# CTRL_LOGIC.net
KiCad netlist of a schematic drawn in Altium Designer
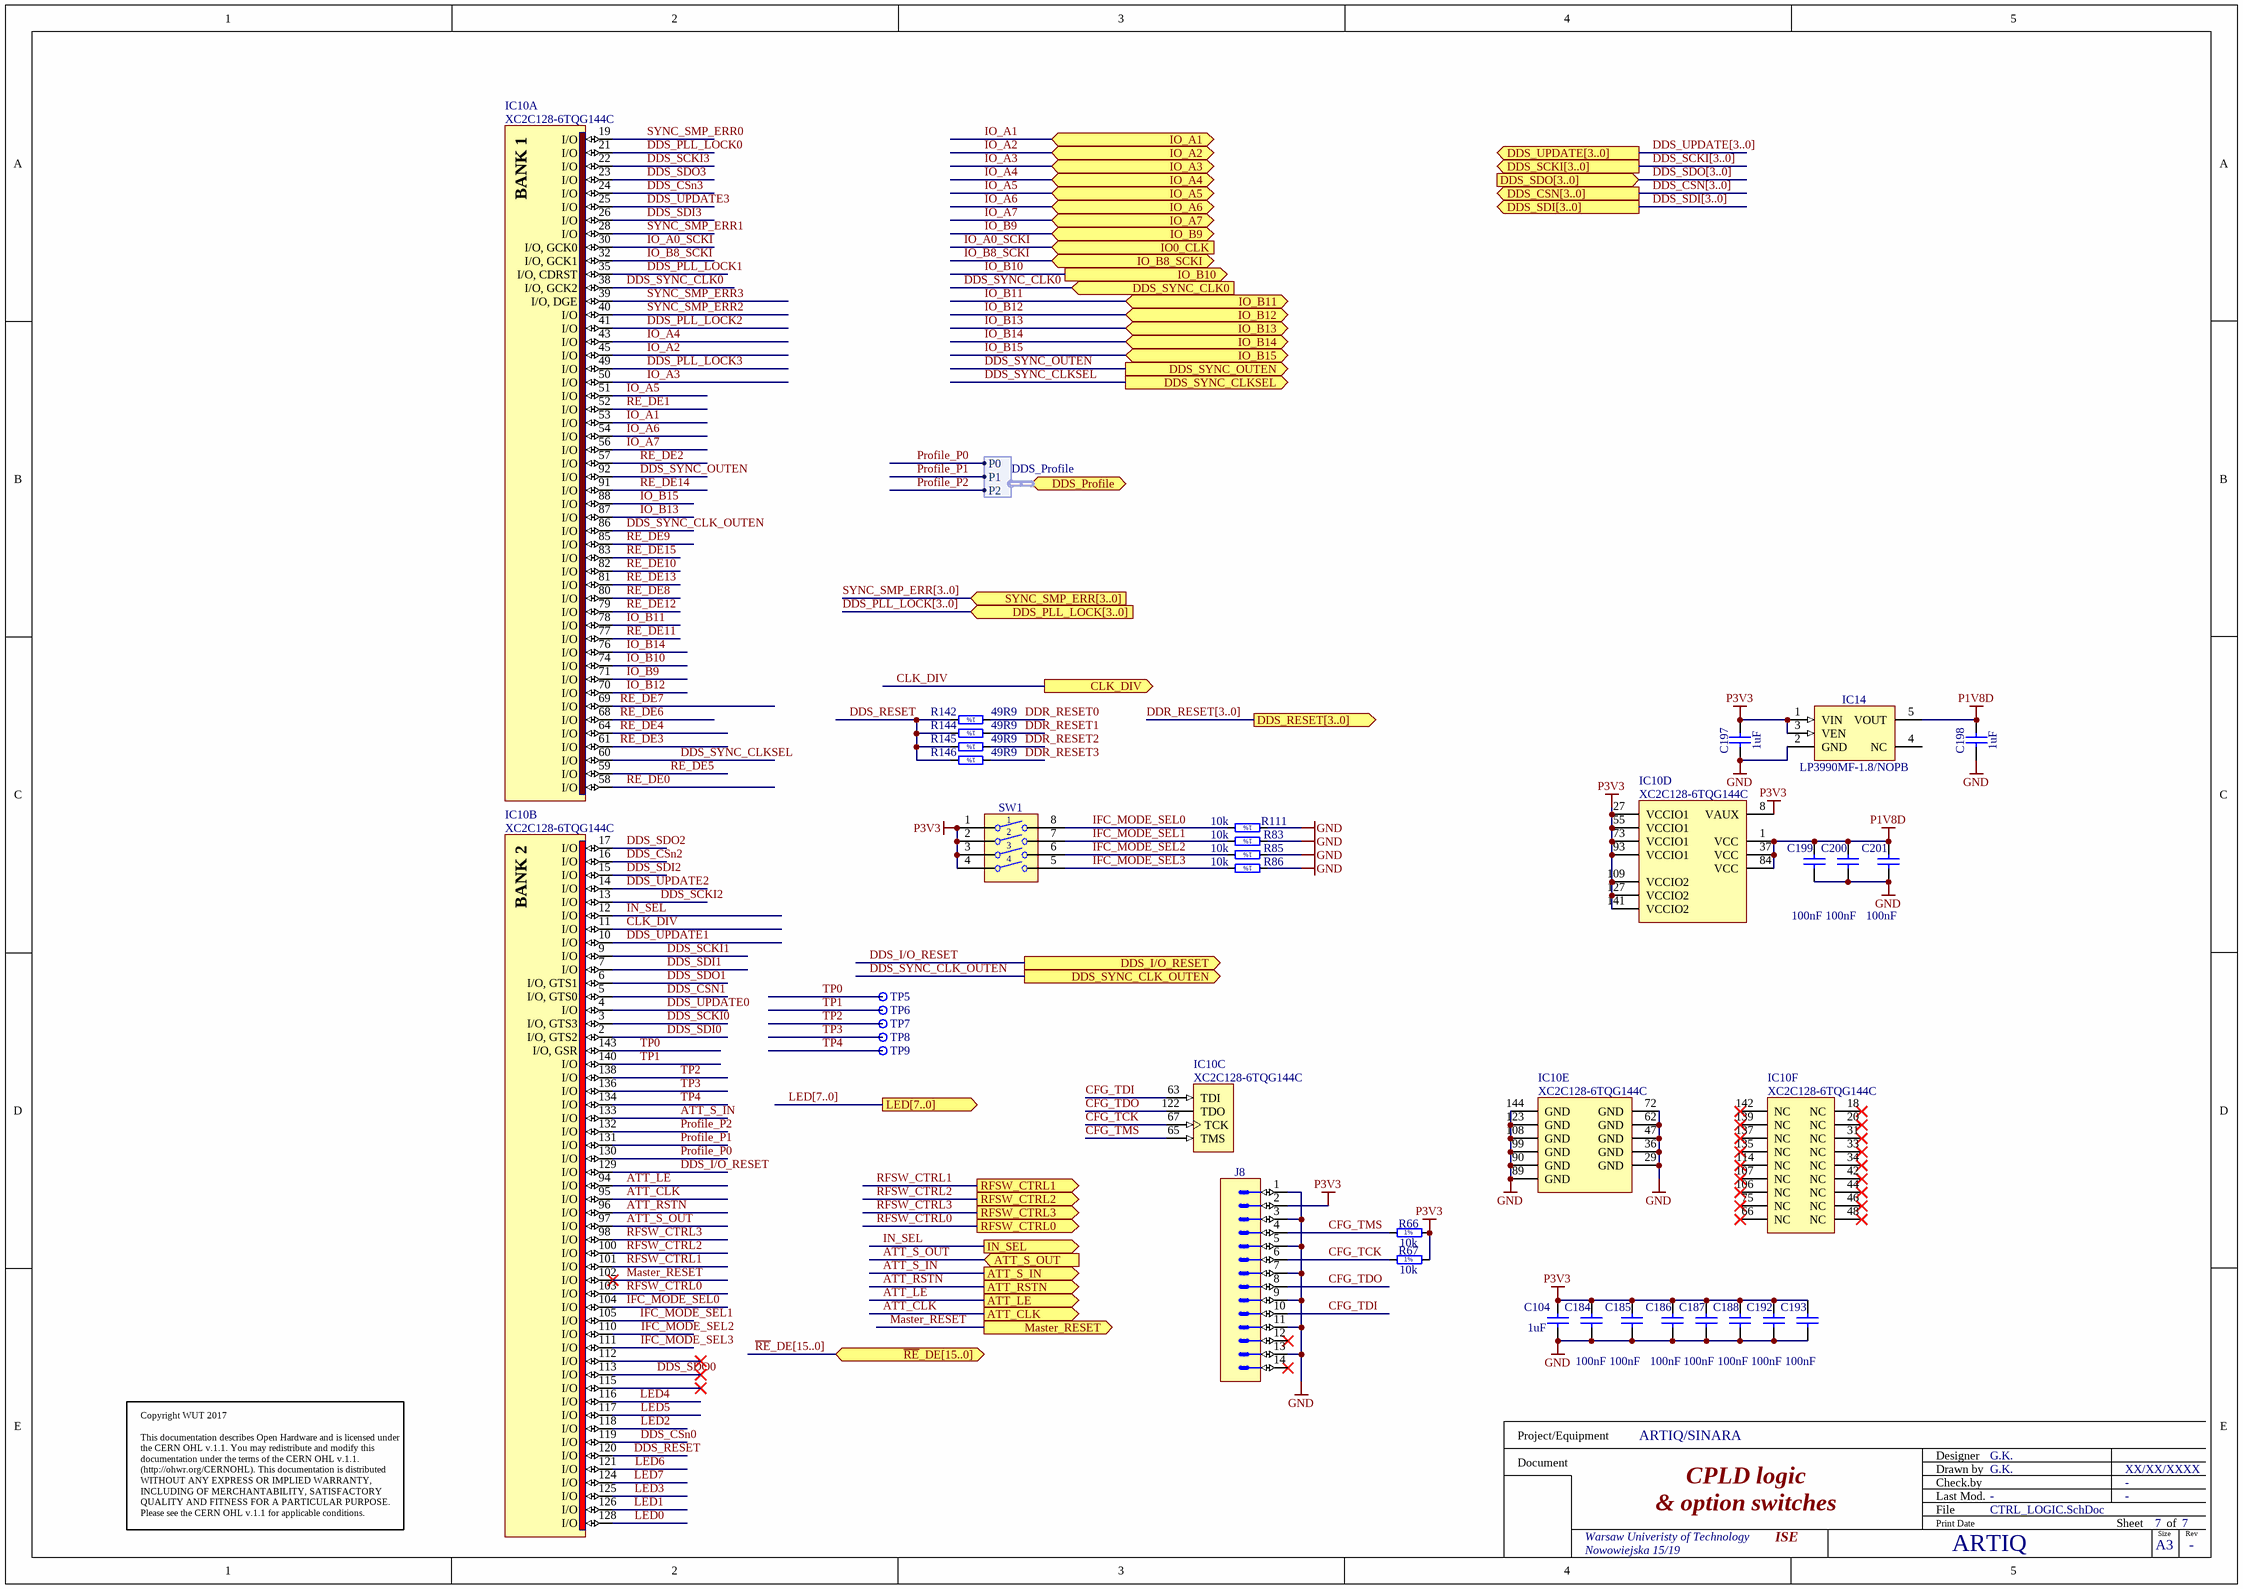
[diagram p0: CTRL_LOGIC.SchDoc]

(export (version "E")
  (design (tool "Eeschema 10.0.6"))
  (components
    (comp (ref "C104")
      (value "1uF")
      (footprint "CAPC1005X55N")
      (description "Non-polarised capacitor")
      (fields
        (field (name "PART NUMBER") "CC0402_1UF_16V_10%_X5R")
        (field (name "VOLTAGE") "16V")
        (field (name "AUTHOR") "CERN DEM JLC")
      )
      (libsource (lib "Capacitors") (part "Capacitor - non polarized"))
    )
    (comp (ref "C184")
      (value "100nF")
      (footprint "CAPC1005X55N")
      (description "Non-polarised capacitor")
      (fields
        (field (name "PART NUMBER") "CC0402_100NF_16V_10%_X5R")
        (field (name "VOLTAGE") "16V")
        (field (name "AUTHOR") "CERN DEM JLC")
      )
      (libsource (lib "Capacitors") (part "Capacitor - non polarized"))
    )
    (comp (ref "C185")
      (value "100nF")
      (footprint "CAPC1005X55N")
      (description "Non-polarised capacitor")
      (fields
        (field (name "PART NUMBER") "CC0402_100NF_16V_10%_X5R")
        (field (name "VOLTAGE") "16V")
        (field (name "AUTHOR") "CERN DEM JLC")
      )
      (libsource (lib "Capacitors") (part "Capacitor - non polarized"))
    )
    (comp (ref "C186")
      (value "100nF")
      (footprint "CAPC1005X55N")
      (description "Non-polarised capacitor")
      (fields
        (field (name "PART NUMBER") "CC0402_100NF_16V_10%_X5R")
        (field (name "VOLTAGE") "16V")
        (field (name "AUTHOR") "CERN DEM JLC")
      )
      (libsource (lib "Capacitors") (part "Capacitor - non polarized"))
    )
    (comp (ref "C187")
      (value "100nF")
      (footprint "CAPC1005X55N")
      (description "Non-polarised capacitor")
      (fields
        (field (name "PART NUMBER") "CC0402_100NF_16V_10%_X5R")
        (field (name "VOLTAGE") "16V")
        (field (name "AUTHOR") "CERN DEM JLC")
      )
      (libsource (lib "Capacitors") (part "Capacitor - non polarized"))
    )
    (comp (ref "C188")
      (value "100nF")
      (footprint "CAPC1005X55N")
      (description "Non-polarised capacitor")
      (fields
        (field (name "PART NUMBER") "CC0402_100NF_16V_10%_X5R")
        (field (name "VOLTAGE") "16V")
        (field (name "AUTHOR") "CERN DEM JLC")
      )
      (libsource (lib "Capacitors") (part "Capacitor - non polarized"))
    )
    (comp (ref "C192")
      (value "100nF")
      (footprint "CAPC1005X55N")
      (description "Non-polarised capacitor")
      (fields
        (field (name "PART NUMBER") "CC0402_100NF_16V_10%_X5R")
        (field (name "VOLTAGE") "16V")
        (field (name "AUTHOR") "CERN DEM JLC")
      )
      (libsource (lib "Capacitors") (part "Capacitor - non polarized"))
    )
    (comp (ref "C193")
      (value "100nF")
      (footprint "CAPC1005X55N")
      (description "Non-polarised capacitor")
      (fields
        (field (name "PART NUMBER") "CC0402_100NF_16V_10%_X5R")
        (field (name "VOLTAGE") "16V")
        (field (name "AUTHOR") "CERN DEM JLC")
      )
      (libsource (lib "Capacitors") (part "Capacitor - non polarized"))
    )
    (comp (ref "C197")
      (value "1uF")
      (footprint "CAPC1005X55N")
      (description "Non-polarised capacitor")
      (fields
        (field (name "PART NUMBER") "CC0402_1UF_16V_10%_X5R")
        (field (name "VOLTAGE") "16V")
        (field (name "AUTHOR") "CERN DEM JLC")
      )
      (libsource (lib "Capacitors") (part "Capacitor - non polarized"))
    )
    (comp (ref "C198")
      (value "1uF")
      (footprint "CAPC1005X55N")
      (description "Non-polarised capacitor")
      (fields
        (field (name "PART NUMBER") "CC0402_1UF_16V_10%_X5R")
        (field (name "VOLTAGE") "16V")
        (field (name "AUTHOR") "CERN DEM JLC")
      )
      (libsource (lib "Capacitors") (part "Capacitor - non polarized"))
    )
    (comp (ref "C199")
      (value "100nF")
      (footprint "CAPC1005X55N")
      (description "Non-polarised capacitor")
      (fields
        (field (name "PART NUMBER") "CC0402_100NF_16V_10%_X5R")
        (field (name "VOLTAGE") "16V")
        (field (name "AUTHOR") "CERN DEM JLC")
      )
      (libsource (lib "Capacitors") (part "Capacitor - non polarized"))
    )
    (comp (ref "C200")
      (value "100nF")
      (footprint "CAPC1005X55N")
      (description "Non-polarised capacitor")
      (fields
        (field (name "PART NUMBER") "CC0402_100NF_16V_10%_X5R")
        (field (name "VOLTAGE") "16V")
        (field (name "AUTHOR") "CERN DEM JLC")
      )
      (libsource (lib "Capacitors") (part "Capacitor - non polarized"))
    )
    (comp (ref "C201")
      (value "100nF")
      (footprint "CAPC1005X55N")
      (description "Non-polarised capacitor")
      (fields
        (field (name "PART NUMBER") "CC0402_100NF_16V_10%_X5R")
        (field (name "VOLTAGE") "16V")
        (field (name "AUTHOR") "CERN DEM JLC")
      )
      (libsource (lib "Capacitors") (part "Capacitor - non polarized"))
    )
    (comp (ref "IC10")
      (value "XC2C128-6TQG144C")
      (footprint "QFP50P2200X2200X160-144N")
      (description "CoolRunner-II 1.8V, 128 Macrocell CPLD, 100 User I/Os, 144-Pin TQFP, Commercial Grade, Pb-Free")
      (fields (field (name "MANUFACTURER") "XILINX") (field (name "AUTHOR") "CERN DEM JLC"))
      (libsource (lib "ICs And Semiconductors") (part "XC2C128-6TQG144C"))
    )
    (comp (ref "IC14")
      (value "LP3990MF-1.8/NOPB")
      (footprint "SOT95P284X122-5N")
      (description "1.8V, 150mA Linear Voltage Regulator For Digital Applications")
      (fields (field (name "MANUFACTURER") "TEXAS INSTRUMENTS") (field (name "AUTHOR") "CERN DEM JLC"))
      (libsource (lib "ICs And Semiconductors") (part "LP3990MF"))
    )
    (comp (ref "J8")
      (value "Milli-Grid™")
      (footprint "MOLEX_87832-1420")
      (description "Connector 14 Male")
      (fields
        (field (name "PART NUMBER") "MOLEX_87832-1420")
        (field (name "MANUFACTURER") "MOLEX")
        (field (name "AUTHOR") "CERN DEM JLC")
      )
      (libsource (lib "Connectors") (part "Connector 14 Male"))
    )
    (comp (ref "R66")
      (value "10k")
      (footprint "RESC1005X40N")
      (description "Resistor - 1%")
      (fields
        (field (name "PART NUMBER") "R0402_10K_1%_0.0625W_100PPM")
        (field (name "POWER") "0.0625W")
        (field (name "AUTHOR") "CERN DEM JLC")
      )
      (libsource (lib "Resistors") (part "Resistor - 1%"))
    )
    (comp (ref "R67")
      (value "10k")
      (footprint "RESC1005X40N")
      (description "Resistor - 1%")
      (fields
        (field (name "PART NUMBER") "R0402_10K_1%_0.0625W_100PPM")
        (field (name "POWER") "0.0625W")
        (field (name "AUTHOR") "CERN DEM JLC")
      )
      (libsource (lib "Resistors") (part "Resistor - 1%"))
    )
    (comp (ref "R83")
      (value "10k")
      (footprint "RESC1005X40N")
      (description "Resistor - 1%")
      (fields
        (field (name "PART NUMBER") "R0402_10K_1%_0.0625W_100PPM")
        (field (name "POWER") "0.0625W")
        (field (name "AUTHOR") "CERN DEM JLC")
      )
      (libsource (lib "Resistors") (part "Resistor - 1%"))
    )
    (comp (ref "R85")
      (value "10k")
      (footprint "RESC1005X40N")
      (description "Resistor - 1%")
      (fields
        (field (name "PART NUMBER") "R0402_10K_1%_0.0625W_100PPM")
        (field (name "POWER") "0.0625W")
        (field (name "AUTHOR") "CERN DEM JLC")
      )
      (libsource (lib "Resistors") (part "Resistor - 1%"))
    )
    (comp (ref "R86")
      (value "10k")
      (footprint "RESC1005X40N")
      (description "Resistor - 1%")
      (fields
        (field (name "PART NUMBER") "R0402_10K_1%_0.0625W_100PPM")
        (field (name "POWER") "0.0625W")
        (field (name "AUTHOR") "CERN DEM JLC")
      )
      (libsource (lib "Resistors") (part "Resistor - 1%"))
    )
    (comp (ref "R111")
      (value "10k")
      (footprint "RESC1005X40N")
      (description "Resistor - 1%")
      (fields
        (field (name "PART NUMBER") "R0402_10K_1%_0.0625W_100PPM")
        (field (name "POWER") "0.0625W")
        (field (name "AUTHOR") "CERN DEM JLC")
      )
      (libsource (lib "Resistors") (part "Resistor - 1%"))
    )
    (comp (ref "R142")
      (value "49R9")
      (footprint "RESC1005X40N")
      (description "Resistor - 1%")
      (fields
        (field (name "PART NUMBER") "R0402_49R9_1%_0.0625W_100PPM")
        (field (name "POWER") "0.0625W")
        (field (name "AUTHOR") "CERN DEM JLC")
      )
      (libsource (lib "Resistors") (part "Resistor - 1%"))
    )
    (comp (ref "R144")
      (value "49R9")
      (footprint "RESC1005X40N")
      (description "Resistor - 1%")
      (fields
        (field (name "PART NUMBER") "R0402_49R9_1%_0.0625W_100PPM")
        (field (name "POWER") "0.0625W")
        (field (name "AUTHOR") "CERN DEM JLC")
      )
      (libsource (lib "Resistors") (part "Resistor - 1%"))
    )
    (comp (ref "R145")
      (value "49R9")
      (footprint "RESC1005X40N")
      (description "Resistor - 1%")
      (fields
        (field (name "PART NUMBER") "R0402_49R9_1%_0.0625W_100PPM")
        (field (name "POWER") "0.0625W")
        (field (name "AUTHOR") "CERN DEM JLC")
      )
      (libsource (lib "Resistors") (part "Resistor - 1%"))
    )
    (comp (ref "R146")
      (value "49R9")
      (footprint "RESC1005X40N")
      (description "Resistor - 1%")
      (fields
        (field (name "PART NUMBER") "R0402_49R9_1%_0.0625W_100PPM")
        (field (name "POWER") "0.0625W")
        (field (name "AUTHOR") "CERN DEM JLC")
      )
      (libsource (lib "Resistors") (part "Resistor - 1%"))
    )
    (comp (ref "SW1")
      (value "Switch")
      (footprint "SW_OMRON_A6S-4102-H")
      (description "4 Ways SPST DIP Switch")
      (fields
        (field (name "PART NUMBER") "SW_OMRON_A6S-4102-H")
        (field (name "MANUFACTURER") "OMRON")
        (field (name "AUTHOR") "CERN DEM JMW")
      )
      (libsource (lib "Eletro-mechanical") (part "SW 4x SPST DIP Switch"))
    )
    (comp (ref "TP5")
      (value "Test Point")
      (footprint "TPS127")
      (fields (field (name "PART NUMBER") "SMD_PAD_1.27X1.27MM") (field (name "AUTHOR") "CERN DEM JLC"))
      (libsource (lib "Eletro-mechanical") (part "Test Point"))
    )
    (comp (ref "TP6")
      (value "Test Point")
      (footprint "TPS127")
      (fields (field (name "PART NUMBER") "SMD_PAD_1.27X1.27MM") (field (name "AUTHOR") "CERN DEM JLC"))
      (libsource (lib "Eletro-mechanical") (part "Test Point"))
    )
    (comp (ref "TP7")
      (value "Test Point")
      (footprint "TPS127")
      (fields (field (name "PART NUMBER") "SMD_PAD_1.27X1.27MM") (field (name "AUTHOR") "CERN DEM JLC"))
      (libsource (lib "Eletro-mechanical") (part "Test Point"))
    )
    (comp (ref "TP8")
      (value "Test Point")
      (footprint "TPS127")
      (fields (field (name "PART NUMBER") "SMD_PAD_1.27X1.27MM") (field (name "AUTHOR") "CERN DEM JLC"))
      (libsource (lib "Eletro-mechanical") (part "Test Point"))
    )
    (comp (ref "TP9")
      (value "Test Point")
      (footprint "TPS127")
      (fields (field (name "PART NUMBER") "SMD_PAD_1.27X1.27MM") (field (name "AUTHOR") "CERN DEM JLC"))
      (libsource (lib "Eletro-mechanical") (part "Test Point"))
    )
  )
  (nets
    (net (code "5") (name "/ATT_CLK") (class "Default")
      (node (ref "IC10") (pin "95") (pinfunction "I/O_95") (pintype "bidirectional"))
    )
    (net (code "6") (name "/ATT_LE") (class "Default")
      (node (ref "IC10") (pin "94") (pinfunction "I/O_94") (pintype "bidirectional"))
    )
    (net (code "7") (name "/ATT_RSTN") (class "Default")
      (node (ref "IC10") (pin "96") (pinfunction "I/O_96") (pintype "bidirectional"))
    )
    (net (code "8") (name "/ATT_S_IN") (class "Default")
      (node (ref "IC10") (pin "133") (pinfunction "I/O_133") (pintype "bidirectional"))
    )
    (net (code "9") (name "/ATT_S_OUT") (class "Default")
      (node (ref "IC10") (pin "97") (pinfunction "I/O_97") (pintype "bidirectional"))
    )
    (net (code "10") (name "/CFG_TCK") (class "Default")
      (node (ref "IC10") (pin "67") (pinfunction "TCK_67") (pintype "input"))
      (node (ref "J8") (pin "6") (pinfunction "6_6") (pintype "bidirectional"))
      (node (ref "R67") (pin "1") (pinfunction "1_1") (pintype "passive"))
    )
    (net (code "11") (name "/CFG_TDI") (class "Default")
      (node (ref "IC10") (pin "63") (pinfunction "TDI_63") (pintype "input"))
      (node (ref "J8") (pin "10") (pinfunction "10_10") (pintype "bidirectional"))
    )
    (net (code "12") (name "/CFG_TDO") (class "Default")
      (node (ref "IC10") (pin "122") (pinfunction "TDO_122") (pintype "passive"))
      (node (ref "J8") (pin "8") (pinfunction "8_8") (pintype "bidirectional"))
    )
    (net (code "13") (name "/CFG_TMS") (class "Default")
      (node (ref "IC10") (pin "65") (pinfunction "TMS_65") (pintype "input"))
      (node (ref "J8") (pin "4") (pinfunction "4_4") (pintype "bidirectional"))
      (node (ref "R66") (pin "1") (pinfunction "1_1") (pintype "passive"))
    )
    (net (code "14") (name "/CLK_DIV") (class "Default")
      (node (ref "IC10") (pin "11") (pinfunction "I/O_11") (pintype "bidirectional"))
    )
    (net (code "15") (name "/DDR_RESET0") (class "Default")
      (node (ref "R142") (pin "1") (pinfunction "1_1") (pintype "passive"))
    )
    (net (code "16") (name "/DDR_RESET1") (class "Default")
      (node (ref "R144") (pin "1") (pinfunction "1_1") (pintype "passive"))
    )
    (net (code "17") (name "/DDR_RESET2") (class "Default")
      (node (ref "R145") (pin "1") (pinfunction "1_1") (pintype "passive"))
    )
    (net (code "18") (name "/DDR_RESET3") (class "Default")
      (node (ref "R146") (pin "1") (pinfunction "1_1") (pintype "passive"))
    )
    (net (code "20") (name "/DDS_CSN1") (class "Default")
      (node (ref "IC10") (pin "5") (pinfunction "I/O,_GTS0_5") (pintype "bidirectional"))
    )
    (net (code "22") (name "/DDS_CSn0") (class "Default")
      (node (ref "IC10") (pin "119") (pinfunction "I/O_119") (pintype "bidirectional"))
    )
    (net (code "23") (name "/DDS_CSn2") (class "Default")
      (node (ref "IC10") (pin "16") (pinfunction "I/O_16") (pintype "bidirectional"))
    )
    (net (code "24") (name "/DDS_CSn3") (class "Default")
      (node (ref "IC10") (pin "24") (pinfunction "I/O_24") (pintype "bidirectional"))
    )
    (net (code "25") (name "/DDS_I{slash}O_RESET") (class "Default")
      (node (ref "IC10") (pin "129") (pinfunction "I/O_129") (pintype "bidirectional"))
    )
    (net (code "26") (name "/DDS_PLL_LOCK0") (class "Default")
      (node (ref "IC10") (pin "21") (pinfunction "I/O_21") (pintype "bidirectional"))
    )
    (net (code "27") (name "/DDS_PLL_LOCK1") (class "Default")
      (node (ref "IC10") (pin "35") (pinfunction "I/O,_CDRST_35") (pintype "bidirectional"))
    )
    (net (code "28") (name "/DDS_PLL_LOCK2") (class "Default")
      (node (ref "IC10") (pin "41") (pinfunction "I/O_41") (pintype "bidirectional"))
    )
    (net (code "29") (name "/DDS_PLL_LOCK3") (class "Default")
      (node (ref "IC10") (pin "49") (pinfunction "I/O_49") (pintype "bidirectional"))
    )
    (net (code "31") (name "/DDS_RESET") (class "Default")
      (node (ref "IC10") (pin "120") (pinfunction "I/O_120") (pintype "bidirectional"))
      (node (ref "R142") (pin "2") (pinfunction "2_2") (pintype "passive"))
      (node (ref "R144") (pin "2") (pinfunction "2_2") (pintype "passive"))
      (node (ref "R145") (pin "2") (pinfunction "2_2") (pintype "passive"))
      (node (ref "R146") (pin "2") (pinfunction "2_2") (pintype "passive"))
    )
    (net (code "32") (name "/DDS_SCKI0") (class "Default")
      (node (ref "IC10") (pin "3") (pinfunction "I/O,_GTS3_3") (pintype "bidirectional"))
    )
    (net (code "33") (name "/DDS_SCKI1") (class "Default")
      (node (ref "IC10") (pin "9") (pinfunction "I/O_9") (pintype "bidirectional"))
    )
    (net (code "34") (name "/DDS_SCKI2") (class "Default")
      (node (ref "IC10") (pin "13") (pinfunction "I/O_13") (pintype "bidirectional"))
    )
    (net (code "35") (name "/DDS_SCKI3") (class "Default")
      (node (ref "IC10") (pin "22") (pinfunction "I/O_22") (pintype "bidirectional"))
    )
    (net (code "37") (name "/DDS_SDI0") (class "Default")
      (node (ref "IC10") (pin "2") (pinfunction "I/O,_GTS2_2") (pintype "bidirectional"))
    )
    (net (code "38") (name "/DDS_SDI1") (class "Default")
      (node (ref "IC10") (pin "7") (pinfunction "I/O_7") (pintype "bidirectional"))
    )
    (net (code "39") (name "/DDS_SDI2") (class "Default")
      (node (ref "IC10") (pin "15") (pinfunction "I/O_15") (pintype "bidirectional"))
    )
    (net (code "40") (name "/DDS_SDI3") (class "Default")
      (node (ref "IC10") (pin "26") (pinfunction "I/O_26") (pintype "bidirectional"))
    )
    (net (code "42") (name "/DDS_SDO0") (class "Default")
      (node (ref "IC10") (pin "113") (pinfunction "I/O_113") (pintype "bidirectional+no_connect"))
    )
    (net (code "43") (name "/DDS_SDO1") (class "Default")
      (node (ref "IC10") (pin "6") (pinfunction "I/O,_GTS1_6") (pintype "bidirectional"))
    )
    (net (code "44") (name "/DDS_SDO2") (class "Default")
      (node (ref "IC10") (pin "17") (pinfunction "I/O_17") (pintype "bidirectional"))
    )
    (net (code "45") (name "/DDS_SDO3") (class "Default")
      (node (ref "IC10") (pin "23") (pinfunction "I/O_23") (pintype "bidirectional"))
    )
    (net (code "47") (name "/DDS_SYNC_CLK0") (class "Default")
      (node (ref "IC10") (pin "38") (pinfunction "I/O,_GCK2_38") (pintype "bidirectional"))
    )
    (net (code "48") (name "/DDS_SYNC_CLKSEL") (class "Default")
      (node (ref "IC10") (pin "60") (pinfunction "I/O_60") (pintype "bidirectional"))
    )
    (net (code "49") (name "/DDS_SYNC_CLK_OUTEN") (class "Default")
      (node (ref "IC10") (pin "86") (pinfunction "I/O_86") (pintype "bidirectional"))
    )
    (net (code "50") (name "/DDS_SYNC_OUTEN") (class "Default")
      (node (ref "IC10") (pin "92") (pinfunction "I/O_92") (pintype "bidirectional"))
    )
    (net (code "51") (name "/DDS_UPDATE0") (class "Default")
      (node (ref "IC10") (pin "4") (pinfunction "I/O_4") (pintype "bidirectional"))
    )
    (net (code "52") (name "/DDS_UPDATE1") (class "Default")
      (node (ref "IC10") (pin "10") (pinfunction "I/O_10") (pintype "bidirectional"))
    )
    (net (code "53") (name "/DDS_UPDATE2") (class "Default")
      (node (ref "IC10") (pin "14") (pinfunction "I/O_14") (pintype "bidirectional"))
    )
    (net (code "54") (name "/DDS_UPDATE3") (class "Default")
      (node (ref "IC10") (pin "25") (pinfunction "I/O_25") (pintype "bidirectional"))
    )
    (net (code "56") (name "/IFC_MODE_SEL0") (class "Default")
      (node (ref "IC10") (pin "104") (pinfunction "I/O_104") (pintype "bidirectional"))
      (node (ref "R111") (pin "2") (pinfunction "2_2") (pintype "passive"))
      (node (ref "SW1") (pin "8") (pinfunction "8_8") (pintype "passive"))
    )
    (net (code "57") (name "/IFC_MODE_SEL1") (class "Default")
      (node (ref "IC10") (pin "105") (pinfunction "I/O_105") (pintype "bidirectional"))
      (node (ref "R83") (pin "2") (pinfunction "2_2") (pintype "passive"))
      (node (ref "SW1") (pin "7") (pinfunction "7_7") (pintype "passive"))
    )
    (net (code "58") (name "/IFC_MODE_SEL2") (class "Default")
      (node (ref "IC10") (pin "110") (pinfunction "I/O_110") (pintype "bidirectional"))
      (node (ref "R85") (pin "2") (pinfunction "2_2") (pintype "passive"))
      (node (ref "SW1") (pin "6") (pinfunction "6_6") (pintype "passive"))
    )
    (net (code "59") (name "/IFC_MODE_SEL3") (class "Default")
      (node (ref "IC10") (pin "111") (pinfunction "I/O_111") (pintype "bidirectional"))
      (node (ref "R86") (pin "2") (pinfunction "2_2") (pintype "passive"))
      (node (ref "SW1") (pin "5") (pinfunction "5_5") (pintype "passive"))
    )
    (net (code "60") (name "/IN_SEL") (class "Default")
      (node (ref "IC10") (pin "12") (pinfunction "I/O_12") (pintype "bidirectional"))
    )
    (net (code "61") (name "/IO_A0_SCKI") (class "Default")
      (node (ref "IC10") (pin "30") (pinfunction "I/O,_GCK0_30") (pintype "bidirectional"))
    )
    (net (code "62") (name "/IO_A1") (class "Default")
      (node (ref "IC10") (pin "53") (pinfunction "I/O_53") (pintype "bidirectional"))
    )
    (net (code "63") (name "/IO_A2") (class "Default")
      (node (ref "IC10") (pin "45") (pinfunction "I/O_45") (pintype "bidirectional"))
    )
    (net (code "64") (name "/IO_A3") (class "Default")
      (node (ref "IC10") (pin "50") (pinfunction "I/O_50") (pintype "bidirectional"))
    )
    (net (code "65") (name "/IO_A4") (class "Default")
      (node (ref "IC10") (pin "43") (pinfunction "I/O_43") (pintype "bidirectional"))
    )
    (net (code "66") (name "/IO_A5") (class "Default")
      (node (ref "IC10") (pin "51") (pinfunction "I/O_51") (pintype "bidirectional"))
    )
    (net (code "67") (name "/IO_A6") (class "Default")
      (node (ref "IC10") (pin "54") (pinfunction "I/O_54") (pintype "bidirectional"))
    )
    (net (code "68") (name "/IO_A7") (class "Default")
      (node (ref "IC10") (pin "56") (pinfunction "I/O_56") (pintype "bidirectional"))
    )
    (net (code "69") (name "/IO_B8_SCKI") (class "Default")
      (node (ref "IC10") (pin "32") (pinfunction "I/O,_GCK1_32") (pintype "bidirectional"))
    )
    (net (code "70") (name "/IO_B9") (class "Default")
      (node (ref "IC10") (pin "71") (pinfunction "I/O_71") (pintype "bidirectional"))
    )
    (net (code "71") (name "/IO_B10") (class "Default")
      (node (ref "IC10") (pin "74") (pinfunction "I/O_74") (pintype "bidirectional"))
    )
    (net (code "72") (name "/IO_B11") (class "Default")
      (node (ref "IC10") (pin "78") (pinfunction "I/O_78") (pintype "bidirectional"))
    )
    (net (code "73") (name "/IO_B12") (class "Default")
      (node (ref "IC10") (pin "70") (pinfunction "I/O_70") (pintype "bidirectional"))
    )
    (net (code "74") (name "/IO_B13") (class "Default")
      (node (ref "IC10") (pin "87") (pinfunction "I/O_87") (pintype "bidirectional"))
    )
    (net (code "75") (name "/IO_B14") (class "Default")
      (node (ref "IC10") (pin "76") (pinfunction "I/O_76") (pintype "bidirectional"))
    )
    (net (code "76") (name "/IO_B15") (class "Default")
      (node (ref "IC10") (pin "88") (pinfunction "I/O_88") (pintype "bidirectional"))
    )
    (net (code "77") (name "/LED0") (class "Default")
      (node (ref "IC10") (pin "128") (pinfunction "I/O_128") (pintype "bidirectional"))
    )
    (net (code "78") (name "/LED1") (class "Default")
      (node (ref "IC10") (pin "126") (pinfunction "I/O_126") (pintype "bidirectional"))
    )
    (net (code "79") (name "/LED2") (class "Default")
      (node (ref "IC10") (pin "118") (pinfunction "I/O_118") (pintype "bidirectional"))
    )
    (net (code "80") (name "/LED3") (class "Default")
      (node (ref "IC10") (pin "125") (pinfunction "I/O_125") (pintype "bidirectional"))
    )
    (net (code "81") (name "/LED4") (class "Default")
      (node (ref "IC10") (pin "116") (pinfunction "I/O_116") (pintype "bidirectional"))
    )
    (net (code "82") (name "/LED5") (class "Default")
      (node (ref "IC10") (pin "117") (pinfunction "I/O_117") (pintype "bidirectional"))
    )
    (net (code "83") (name "/LED6") (class "Default")
      (node (ref "IC10") (pin "121") (pinfunction "I/O_121") (pintype "bidirectional"))
    )
    (net (code "84") (name "/LED7") (class "Default")
      (node (ref "IC10") (pin "124") (pinfunction "I/O_124") (pintype "bidirectional"))
    )
    (net (code "86") (name "/Master_RESET") (class "Default")
      (node (ref "IC10") (pin "102") (pinfunction "I/O_102") (pintype "bidirectional+no_connect"))
    )
    (net (code "87") (name "/Profile_P0") (class "Default")
      (node (ref "IC10") (pin "130") (pinfunction "I/O_130") (pintype "bidirectional"))
    )
    (net (code "88") (name "/Profile_P1") (class "Default")
      (node (ref "IC10") (pin "131") (pinfunction "I/O_131") (pintype "bidirectional"))
    )
    (net (code "89") (name "/Profile_P2") (class "Default")
      (node (ref "IC10") (pin "132") (pinfunction "I/O_132") (pintype "bidirectional"))
    )
    (net (code "90") (name "/RFSW_CTRL0") (class "Default")
      (node (ref "IC10") (pin "103") (pinfunction "I/O_103") (pintype "bidirectional"))
    )
    (net (code "91") (name "/RFSW_CTRL1") (class "Default")
      (node (ref "IC10") (pin "101") (pinfunction "I/O_101") (pintype "bidirectional"))
    )
    (net (code "92") (name "/RFSW_CTRL2") (class "Default")
      (node (ref "IC10") (pin "100") (pinfunction "I/O_100") (pintype "bidirectional"))
    )
    (net (code "93") (name "/RFSW_CTRL3") (class "Default")
      (node (ref "IC10") (pin "98") (pinfunction "I/O_98") (pintype "bidirectional"))
    )
    (net (code "94") (name "/SYNC_SMP_ERR0") (class "Default")
      (node (ref "IC10") (pin "19") (pinfunction "I/O_19") (pintype "bidirectional"))
    )
    (net (code "95") (name "/SYNC_SMP_ERR1") (class "Default")
      (node (ref "IC10") (pin "28") (pinfunction "I/O_28") (pintype "bidirectional"))
    )
    (net (code "96") (name "/SYNC_SMP_ERR2") (class "Default")
      (node (ref "IC10") (pin "40") (pinfunction "I/O_40") (pintype "bidirectional"))
    )
    (net (code "97") (name "/SYNC_SMP_ERR3") (class "Default")
      (node (ref "IC10") (pin "39") (pinfunction "I/O,_DGE_39") (pintype "bidirectional"))
    )
    (net (code "99") (name "/TP0") (class "Default")
      (node (ref "IC10") (pin "143") (pinfunction "I/O,_GSR_143") (pintype "bidirectional"))
      (node (ref "TP5") (pin "1") (pinfunction "1_1") (pintype "bidirectional"))
    )
    (net (code "100") (name "/TP1") (class "Default")
      (node (ref "IC10") (pin "140") (pinfunction "I/O_140") (pintype "bidirectional"))
      (node (ref "TP6") (pin "1") (pinfunction "1_1") (pintype "bidirectional"))
    )
    (net (code "101") (name "/TP2") (class "Default")
      (node (ref "IC10") (pin "138") (pinfunction "I/O_138") (pintype "bidirectional"))
      (node (ref "TP7") (pin "1") (pinfunction "1_1") (pintype "bidirectional"))
    )
    (net (code "102") (name "/TP3") (class "Default")
      (node (ref "IC10") (pin "136") (pinfunction "I/O_136") (pintype "bidirectional"))
      (node (ref "TP8") (pin "1") (pinfunction "1_1") (pintype "bidirectional"))
    )
    (net (code "103") (name "/TP4") (class "Default")
      (node (ref "IC10") (pin "134") (pinfunction "I/O_134") (pintype "bidirectional"))
      (node (ref "TP9") (pin "1") (pinfunction "1_1") (pintype "bidirectional"))
    )
    (net (code "105") (name "/~{RE}_DE0") (class "Default")
      (node (ref "IC10") (pin "58") (pinfunction "I/O_58") (pintype "bidirectional"))
    )
    (net (code "106") (name "/~{RE}_DE1") (class "Default")
      (node (ref "IC10") (pin "52") (pinfunction "I/O_52") (pintype "bidirectional"))
    )
    (net (code "107") (name "/~{RE}_DE2") (class "Default")
      (node (ref "IC10") (pin "57") (pinfunction "I/O_57") (pintype "bidirectional"))
    )
    (net (code "108") (name "/~{RE}_DE3") (class "Default")
      (node (ref "IC10") (pin "61") (pinfunction "I/O_61") (pintype "bidirectional"))
    )
    (net (code "109") (name "/~{RE}_DE4") (class "Default")
      (node (ref "IC10") (pin "64") (pinfunction "I/O_64") (pintype "bidirectional"))
    )
    (net (code "110") (name "/~{RE}_DE5") (class "Default")
      (node (ref "IC10") (pin "59") (pinfunction "I/O_59") (pintype "bidirectional"))
    )
    (net (code "111") (name "/~{RE}_DE6") (class "Default")
      (node (ref "IC10") (pin "68") (pinfunction "I/O_68") (pintype "bidirectional"))
    )
    (net (code "112") (name "/~{RE}_DE7") (class "Default")
      (node (ref "IC10") (pin "69") (pinfunction "I/O_69") (pintype "bidirectional"))
    )
    (net (code "113") (name "/~{RE}_DE8") (class "Default")
      (node (ref "IC10") (pin "80") (pinfunction "I/O_80") (pintype "bidirectional"))
    )
    (net (code "114") (name "/~{RE}_DE9") (class "Default")
      (node (ref "IC10") (pin "85") (pinfunction "I/O_85") (pintype "bidirectional"))
    )
    (net (code "115") (name "/~{RE}_DE10") (class "Default")
      (node (ref "IC10") (pin "82") (pinfunction "I/O_82") (pintype "bidirectional"))
    )
    (net (code "116") (name "/~{RE}_DE11") (class "Default")
      (node (ref "IC10") (pin "77") (pinfunction "I/O_77") (pintype "bidirectional"))
    )
    (net (code "117") (name "/~{RE}_DE12") (class "Default")
      (node (ref "IC10") (pin "79") (pinfunction "I/O_79") (pintype "bidirectional"))
    )
    (net (code "118") (name "/~{RE}_DE13") (class "Default")
      (node (ref "IC10") (pin "81") (pinfunction "I/O_81") (pintype "bidirectional"))
    )
    (net (code "119") (name "/~{RE}_DE14") (class "Default")
      (node (ref "IC10") (pin "91") (pinfunction "I/O_91") (pintype "bidirectional"))
    )
    (net (code "120") (name "/~{RE}_DE15") (class "Default")
      (node (ref "IC10") (pin "83") (pinfunction "I/O_83") (pintype "bidirectional"))
    )
    (net (code "122") (name "GND") (class "Default")
      (node (ref "C104") (pin "1") (pinfunction "1_1") (pintype "passive"))
      (node (ref "C184") (pin "1") (pinfunction "1_1") (pintype "passive"))
      (node (ref "C185") (pin "1") (pinfunction "1_1") (pintype "passive"))
      (node (ref "C186") (pin "1") (pinfunction "1_1") (pintype "passive"))
      (node (ref "C187") (pin "1") (pinfunction "1_1") (pintype "passive"))
      (node (ref "C188") (pin "1") (pinfunction "1_1") (pintype "passive"))
      (node (ref "C192") (pin "1") (pinfunction "1_1") (pintype "passive"))
      (node (ref "C193") (pin "1") (pinfunction "1_1") (pintype "passive"))
      (node (ref "C197") (pin "1") (pinfunction "1_1") (pintype "passive"))
      (node (ref "C198") (pin "1") (pinfunction "1_1") (pintype "passive"))
      (node (ref "C199") (pin "1") (pinfunction "1_1") (pintype "passive"))
      (node (ref "C200") (pin "1") (pinfunction "1_1") (pintype "passive"))
      (node (ref "C201") (pin "1") (pinfunction "1_1") (pintype "passive"))
      (node (ref "IC10") (pin "108") (pinfunction "GND_108") (pintype "power_in"))
      (node (ref "IC10") (pin "123") (pinfunction "GND_123") (pintype "power_in"))
      (node (ref "IC10") (pin "144") (pinfunction "GND_144") (pintype "power_in"))
      (node (ref "IC10") (pin "29") (pinfunction "GND_29") (pintype "power_in"))
      (node (ref "IC10") (pin "36") (pinfunction "GND_36") (pintype "power_in"))
      (node (ref "IC10") (pin "47") (pinfunction "GND_47") (pintype "power_in"))
      (node (ref "IC10") (pin "62") (pinfunction "GND_62") (pintype "power_in"))
      (node (ref "IC10") (pin "72") (pinfunction "GND_72") (pintype "power_in"))
      (node (ref "IC10") (pin "89") (pinfunction "GND_89") (pintype "power_in"))
      (node (ref "IC10") (pin "90") (pinfunction "GND_90") (pintype "power_in"))
      (node (ref "IC10") (pin "99") (pinfunction "GND_99") (pintype "power_in"))
      (node (ref "IC14") (pin "2") (pinfunction "GND_2") (pintype "power_in"))
      (node (ref "J8") (pin "1") (pinfunction "1_1") (pintype "bidirectional"))
      (node (ref "J8") (pin "11") (pinfunction "11_11") (pintype "bidirectional"))
      (node (ref "J8") (pin "13") (pinfunction "13_13") (pintype "bidirectional"))
      (node (ref "J8") (pin "3") (pinfunction "3_3") (pintype "bidirectional"))
      (node (ref "J8") (pin "5") (pinfunction "5_5") (pintype "bidirectional"))
      (node (ref "J8") (pin "7") (pinfunction "7_7") (pintype "bidirectional"))
      (node (ref "J8") (pin "9") (pinfunction "9_9") (pintype "bidirectional"))
      (node (ref "R111") (pin "1") (pinfunction "1_1") (pintype "passive"))
      (node (ref "R83") (pin "1") (pinfunction "1_1") (pintype "passive"))
      (node (ref "R85") (pin "1") (pinfunction "1_1") (pintype "passive"))
      (node (ref "R86") (pin "1") (pinfunction "1_1") (pintype "passive"))
    )
    (net (code "123") (name "P1V8D") (class "Default")
      (node (ref "C198") (pin "2") (pinfunction "2_2") (pintype "passive"))
      (node (ref "C199") (pin "2") (pinfunction "2_2") (pintype "passive"))
      (node (ref "C200") (pin "2") (pinfunction "2_2") (pintype "passive"))
      (node (ref "C201") (pin "2") (pinfunction "2_2") (pintype "passive"))
      (node (ref "IC10") (pin "1") (pinfunction "VCC_1") (pintype "power_in"))
      (node (ref "IC10") (pin "37") (pinfunction "VCC_37") (pintype "power_in"))
      (node (ref "IC10") (pin "84") (pinfunction "VCC_84") (pintype "power_in"))
      (node (ref "IC14") (pin "5") (pinfunction "VOUT_5") (pintype "power_in"))
    )
    (net (code "124") (name "P3V3") (class "Default")
      (node (ref "C104") (pin "2") (pinfunction "2_2") (pintype "passive"))
      (node (ref "C184") (pin "2") (pinfunction "2_2") (pintype "passive"))
      (node (ref "C185") (pin "2") (pinfunction "2_2") (pintype "passive"))
      (node (ref "C186") (pin "2") (pinfunction "2_2") (pintype "passive"))
      (node (ref "C187") (pin "2") (pinfunction "2_2") (pintype "passive"))
      (node (ref "C188") (pin "2") (pinfunction "2_2") (pintype "passive"))
      (node (ref "C192") (pin "2") (pinfunction "2_2") (pintype "passive"))
      (node (ref "C193") (pin "2") (pinfunction "2_2") (pintype "passive"))
      (node (ref "C197") (pin "2") (pinfunction "2_2") (pintype "passive"))
      (node (ref "IC10") (pin "109") (pinfunction "VCCIO2_109") (pintype "power_in"))
      (node (ref "IC10") (pin "127") (pinfunction "VCCIO2_127") (pintype "power_in"))
      (node (ref "IC10") (pin "141") (pinfunction "VCCIO2_141") (pintype "power_in"))
      (node (ref "IC10") (pin "27") (pinfunction "VCCIO1_27") (pintype "power_in"))
      (node (ref "IC10") (pin "55") (pinfunction "VCCIO1_55") (pintype "power_in"))
      (node (ref "IC10") (pin "73") (pinfunction "VCCIO1_73") (pintype "power_in"))
      (node (ref "IC10") (pin "8") (pinfunction "VAUX_8") (pintype "power_in"))
      (node (ref "IC10") (pin "93") (pinfunction "VCCIO1_93") (pintype "power_in"))
      (node (ref "IC14") (pin "1") (pinfunction "VIN_1") (pintype "input"))
      (node (ref "IC14") (pin "3") (pinfunction "VEN_3") (pintype "input"))
      (node (ref "J8") (pin "2") (pinfunction "2_2") (pintype "bidirectional"))
      (node (ref "R66") (pin "2") (pinfunction "2_2") (pintype "passive"))
      (node (ref "R67") (pin "2") (pinfunction "2_2") (pintype "passive"))
      (node (ref "SW1") (pin "1") (pinfunction "1_1") (pintype "passive"))
      (node (ref "SW1") (pin "2") (pinfunction "2_2") (pintype "passive"))
      (node (ref "SW1") (pin "3") (pinfunction "3_3") (pintype "passive"))
      (node (ref "SW1") (pin "4") (pinfunction "4_4") (pintype "passive"))
    )
    (net (code "125") (name "unconnected-(IC10B-I{slash}O-Pad112)") (class "Default")
      (node (ref "IC10") (pin "112") (pinfunction "I/O_112") (pintype "bidirectional+no_connect"))
    )
    (net (code "126") (name "unconnected-(IC10B-I{slash}O-Pad115)") (class "Default")
      (node (ref "IC10") (pin "115") (pinfunction "I/O_115") (pintype "bidirectional+no_connect"))
    )
    (net (code "127") (name "unconnected-(IC10F-NC-Pad18)") (class "Default")
      (node (ref "IC10") (pin "18") (pinfunction "NC_18") (pintype "passive+no_connect"))
    )
    (net (code "128") (name "unconnected-(IC10F-NC-Pad20)") (class "Default")
      (node (ref "IC10") (pin "20") (pinfunction "NC_20") (pintype "passive+no_connect"))
    )
    (net (code "129") (name "unconnected-(IC10F-NC-Pad31)") (class "Default")
      (node (ref "IC10") (pin "31") (pinfunction "NC_31") (pintype "passive+no_connect"))
    )
    (net (code "130") (name "unconnected-(IC10F-NC-Pad33)") (class "Default")
      (node (ref "IC10") (pin "33") (pinfunction "NC_33") (pintype "passive+no_connect"))
    )
    (net (code "131") (name "unconnected-(IC10F-NC-Pad34)") (class "Default")
      (node (ref "IC10") (pin "34") (pinfunction "NC_34") (pintype "passive+no_connect"))
    )
    (net (code "132") (name "unconnected-(IC10F-NC-Pad42)") (class "Default")
      (node (ref "IC10") (pin "42") (pinfunction "NC_42") (pintype "passive+no_connect"))
    )
    (net (code "133") (name "unconnected-(IC10F-NC-Pad44)") (class "Default")
      (node (ref "IC10") (pin "44") (pinfunction "NC_44") (pintype "passive+no_connect"))
    )
    (net (code "134") (name "unconnected-(IC10F-NC-Pad46)") (class "Default")
      (node (ref "IC10") (pin "46") (pinfunction "NC_46") (pintype "passive+no_connect"))
    )
    (net (code "135") (name "unconnected-(IC10F-NC-Pad48)") (class "Default")
      (node (ref "IC10") (pin "48") (pinfunction "NC_48") (pintype "passive+no_connect"))
    )
    (net (code "136") (name "unconnected-(IC10F-NC-Pad66)") (class "Default")
      (node (ref "IC10") (pin "66") (pinfunction "NC_66") (pintype "passive+no_connect"))
    )
    (net (code "137") (name "unconnected-(IC10F-NC-Pad75)") (class "Default")
      (node (ref "IC10") (pin "75") (pinfunction "NC_75") (pintype "passive+no_connect"))
    )
    (net (code "138") (name "unconnected-(IC10F-NC-Pad106)") (class "Default")
      (node (ref "IC10") (pin "106") (pinfunction "NC_106") (pintype "passive+no_connect"))
    )
    (net (code "139") (name "unconnected-(IC10F-NC-Pad107)") (class "Default")
      (node (ref "IC10") (pin "107") (pinfunction "NC_107") (pintype "passive+no_connect"))
    )
    (net (code "140") (name "unconnected-(IC10F-NC-Pad114)") (class "Default")
      (node (ref "IC10") (pin "114") (pinfunction "NC_114") (pintype "passive+no_connect"))
    )
    (net (code "141") (name "unconnected-(IC10F-NC-Pad135)") (class "Default")
      (node (ref "IC10") (pin "135") (pinfunction "NC_135") (pintype "passive+no_connect"))
    )
    (net (code "142") (name "unconnected-(IC10F-NC-Pad137)") (class "Default")
      (node (ref "IC10") (pin "137") (pinfunction "NC_137") (pintype "passive+no_connect"))
    )
    (net (code "143") (name "unconnected-(IC10F-NC-Pad139)") (class "Default")
      (node (ref "IC10") (pin "139") (pinfunction "NC_139") (pintype "passive+no_connect"))
    )
    (net (code "144") (name "unconnected-(IC10F-NC-Pad142)") (class "Default")
      (node (ref "IC10") (pin "142") (pinfunction "NC_142") (pintype "passive+no_connect"))
    )
    (net (code "145") (name "unconnected-(IC14-NC-Pad4)") (class "Default")
      (node (ref "IC14") (pin "4") (pinfunction "NC_4") (pintype "passive"))
    )
    (net (code "146") (name "unconnected-(J8-Pad12)") (class "Default")
      (node (ref "J8") (pin "12") (pinfunction "12_12") (pintype "bidirectional+no_connect"))
    )
    (net (code "147") (name "unconnected-(J8-Pad14)") (class "Default")
      (node (ref "J8") (pin "14") (pinfunction "14_14") (pintype "bidirectional+no_connect"))
    )
  )
)
